# OttoPi05b.net
KiCad netlist of a schematic drawn in EAGLE
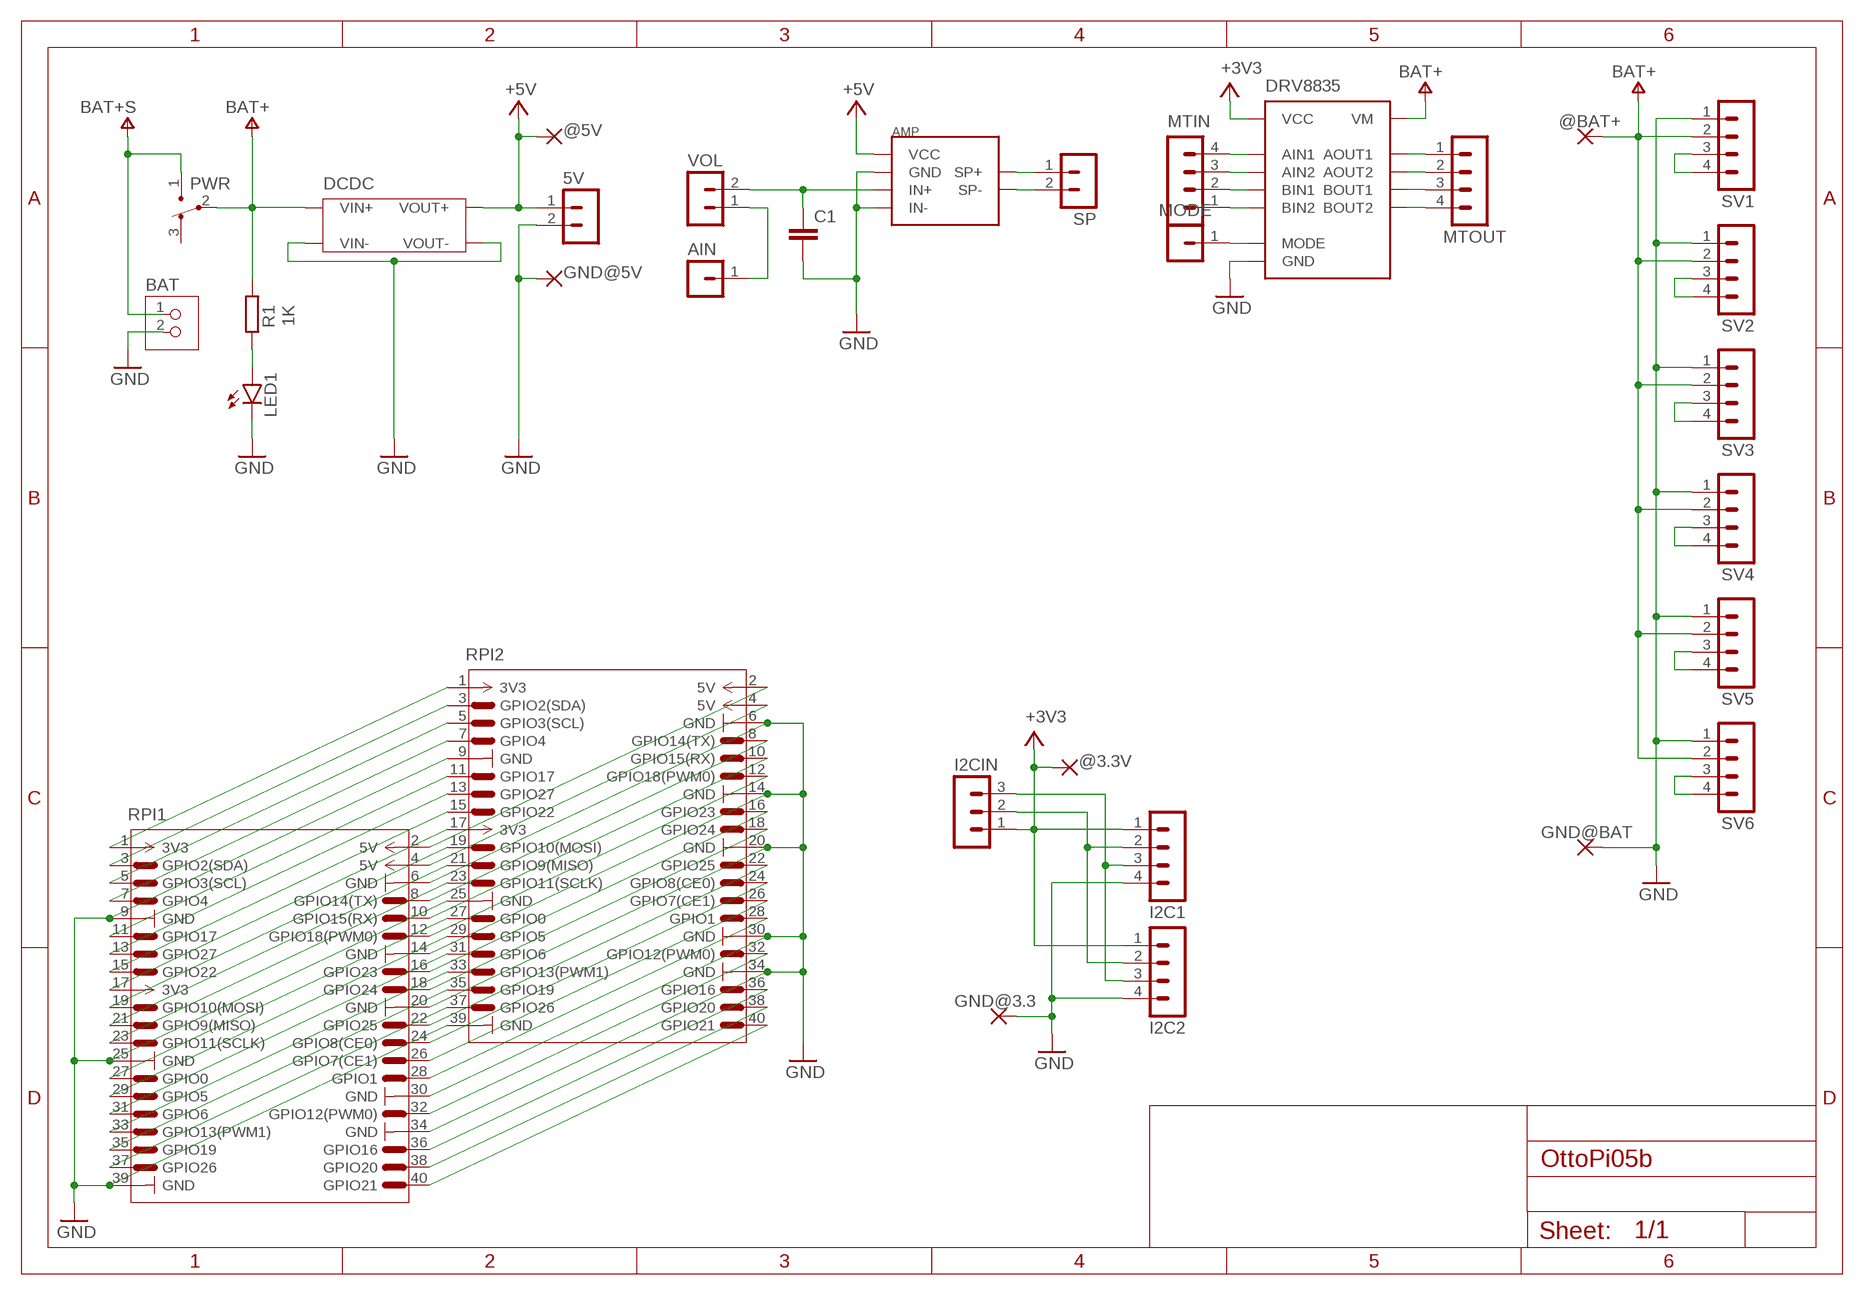
[diagram p0: schematic, sheet 1]

(export (version "E")
  (design (tool "Eeschema 10.0.6"))
  (components
    (comp (ref "5V")
      (value "MA02-1")
      (footprint "eagle-import:MA02-1")
      (libsource (lib "eagle-import") (part "MA02-1"))
    )
    (comp (ref "@3.3V")
      (value "2,15/1,0")
      (footprint "eagle-import:2,15_1,0")
      (libsource (lib "eagle-import") (part "2,15/1,0"))
    )
    (comp (ref "@5V")
      (value "2,15/1,0")
      (footprint "eagle-import:2,15_1,0")
      (libsource (lib "eagle-import") (part "2,15/1,0"))
    )
    (comp (ref "@BAT+")
      (value "2,15/1,0")
      (footprint "eagle-import:2,15_1,0")
      (libsource (lib "eagle-import") (part "2,15/1,0"))
    )
    (comp (ref "AIN")
      (value "MA01-1")
      (footprint "eagle-import:MA01-1")
      (libsource (lib "eagle-import") (part "MA01-1"))
    )
    (comp (ref "AMP")
      (value "PAM8012MOD")
      (footprint "eagle-import:PAM8012MOD-A")
      (libsource (lib "eagle-import") (part "PAM8012MOD"))
    )
    (comp (ref "BAT")
      (value "JST-PH2")
      (footprint "eagle-import:JST-PH2")
      (libsource (lib "eagle-import") (part "JST-PH2"))
    )
    (comp (ref "C1")
      (value "C-EU025-024X044")
      (footprint "eagle-import:C025-024X044")
      (libsource (lib "eagle-import") (part "C-EU025-024X044"))
    )
    (comp (ref "DCDC")
      (value "DCDC-5V_28V-2A")
      (footprint "eagle-import:DCDC-5V_28V-2A")
      (libsource (lib "eagle-import") (part "DCDC-5V_28V-2A"))
    )
    (comp (ref "DRV8835")
      (value "DRV8835MOD")
      (footprint "eagle-import:DRV8835MOD")
      (libsource (lib "eagle-import") (part "DRV8835MOD"))
    )
    (comp (ref "GND@3.3")
      (value "2,15/1,0")
      (footprint "eagle-import:2,15_1,0")
      (libsource (lib "eagle-import") (part "2,15/1,0"))
    )
    (comp (ref "GND@5V")
      (value "2,15/1,0")
      (footprint "eagle-import:2,15_1,0")
      (libsource (lib "eagle-import") (part "2,15/1,0"))
    )
    (comp (ref "GND@BAT")
      (value "2,15/1,0")
      (footprint "eagle-import:2,15_1,0")
      (libsource (lib "eagle-import") (part "2,15/1,0"))
    )
    (comp (ref "I2C1")
      (value "MA04-1")
      (footprint "eagle-import:MA04-1")
      (libsource (lib "eagle-import") (part "MA04-1"))
    )
    (comp (ref "I2C2")
      (value "MA04-1")
      (footprint "eagle-import:MA04-1")
      (libsource (lib "eagle-import") (part "MA04-1"))
    )
    (comp (ref "I2CIN")
      (value "MA03-1")
      (footprint "eagle-import:MA03-1")
      (libsource (lib "eagle-import") (part "MA03-1"))
    )
    (comp (ref "LED1")
      (value "LED3MM")
      (footprint "eagle-import:LED3MM")
      (libsource (lib "eagle-import") (part "LED3MM"))
    )
    (comp (ref "MODE")
      (value "MA01-1")
      (footprint "eagle-import:MA01-1")
      (libsource (lib "eagle-import") (part "MA01-1"))
    )
    (comp (ref "MTIN")
      (value "MA04-1")
      (footprint "eagle-import:MA04-1")
      (libsource (lib "eagle-import") (part "MA04-1"))
    )
    (comp (ref "MTOUT")
      (value "MA04-1")
      (footprint "eagle-import:MA04-1")
      (libsource (lib "eagle-import") (part "MA04-1"))
    )
    (comp (ref "PWR")
      (value "SW3-1")
      (footprint "eagle-import:SW3-1")
      (fields (field (name "MF") "HiLetgo"))
      (libsource (lib "eagle-import") (part "SW3-1"))
    )
    (comp (ref "R1")
      (value "1K")
      (footprint "eagle-import:0204_7")
      (libsource (lib "eagle-import") (part "R-EU_0204/7"))
    )
    (comp (ref "RPI1")
      (value "RPI-PIN")
      (footprint "eagle-import:RPI-PIN")
      (libsource (lib "eagle-import") (part "RPI-PIN"))
    )
    (comp (ref "RPI2")
      (value "RPI-PIN")
      (footprint "eagle-import:RPI-PIN")
      (libsource (lib "eagle-import") (part "RPI-PIN"))
    )
    (comp (ref "SP")
      (value "MA02-1")
      (footprint "eagle-import:MA02-1")
      (libsource (lib "eagle-import") (part "MA02-1"))
    )
    (comp (ref "SV1")
      (value "MA04-1")
      (footprint "eagle-import:MA04-1")
      (libsource (lib "eagle-import") (part "MA04-1"))
    )
    (comp (ref "SV2")
      (value "MA04-1")
      (footprint "eagle-import:MA04-1")
      (libsource (lib "eagle-import") (part "MA04-1"))
    )
    (comp (ref "SV3")
      (value "MA04-1")
      (footprint "eagle-import:MA04-1")
      (libsource (lib "eagle-import") (part "MA04-1"))
    )
    (comp (ref "SV4")
      (value "MA04-1")
      (footprint "eagle-import:MA04-1")
      (libsource (lib "eagle-import") (part "MA04-1"))
    )
    (comp (ref "SV5")
      (value "MA04-1")
      (footprint "eagle-import:MA04-1")
      (libsource (lib "eagle-import") (part "MA04-1"))
    )
    (comp (ref "SV6")
      (value "MA04-1")
      (footprint "eagle-import:MA04-1")
      (libsource (lib "eagle-import") (part "MA04-1"))
    )
    (comp (ref "VOL")
      (value "MA02-1")
      (footprint "eagle-import:MA02-1")
      (libsource (lib "eagle-import") (part "MA02-1"))
    )
  )
  (nets
    (net (code "1") (name "+3V3") (class "Default")
      (node (ref "@3.3V") (pin "1") (pinfunction "P_1") (pintype "passive"))
      (node (ref "DRV8835") (pin "VCC") (pinfunction "VCC_VCC") (pintype "input"))
      (node (ref "I2C1") (pin "1") (pinfunction "1_1") (pintype "passive"))
      (node (ref "I2C2") (pin "1") (pinfunction "1_1") (pintype "passive"))
      (node (ref "I2CIN") (pin "1") (pinfunction "1_1") (pintype "passive"))
    )
    (net (code "2") (name "+5V") (class "Default")
      (node (ref "5V") (pin "1") (pinfunction "1_1") (pintype "passive"))
      (node (ref "@5V") (pin "1") (pinfunction "P_1") (pintype "passive"))
      (node (ref "AMP") (pin "V+") (pinfunction "VCC_V+") (pintype "power_in"))
      (node (ref "DCDC") (pin "VOUT+") (pinfunction "VOUT+_VOUT+") (pintype "power_in"))
    )
    (net (code "3") (name "BAT+") (class "Default")
      (node (ref "@BAT+") (pin "1") (pinfunction "P_1") (pintype "passive"))
      (node (ref "DCDC") (pin "VIN+") (pinfunction "VIN+_VIN+") (pintype "power_in"))
      (node (ref "DRV8835") (pin "VM") (pinfunction "VM_VM") (pintype "input"))
      (node (ref "PWR") (pin "2") (pinfunction "2_2") (pintype "passive"))
      (node (ref "R1") (pin "2") (pinfunction "2_2") (pintype "passive"))
      (node (ref "SV1") (pin "2") (pinfunction "2_2") (pintype "passive"))
      (node (ref "SV2") (pin "2") (pinfunction "2_2") (pintype "passive"))
      (node (ref "SV3") (pin "2") (pinfunction "2_2") (pintype "passive"))
      (node (ref "SV4") (pin "2") (pinfunction "2_2") (pintype "passive"))
      (node (ref "SV5") (pin "2") (pinfunction "2_2") (pintype "passive"))
      (node (ref "SV6") (pin "2") (pinfunction "2_2") (pintype "passive"))
    )
    (net (code "4") (name "BAT+S") (class "Default")
      (node (ref "BAT") (pin "1") (pinfunction "1_1") (pintype "passive"))
      (node (ref "PWR") (pin "1") (pinfunction "1_1") (pintype "passive"))
    )
    (net (code "5") (name "GND") (class "Default")
      (node (ref "5V") (pin "2") (pinfunction "2_2") (pintype "passive"))
      (node (ref "AMP") (pin "GND") (pinfunction "GND_GND") (pintype "power_in"))
      (node (ref "AMP") (pin "IN-") (pinfunction "IN-_IN-") (pintype "input"))
      (node (ref "BAT") (pin "2") (pinfunction "2_2") (pintype "passive"))
      (node (ref "C1") (pin "2") (pinfunction "2_2") (pintype "passive"))
      (node (ref "DCDC") (pin "VIN-") (pinfunction "VIN-_VIN-") (pintype "power_in"))
      (node (ref "DCDC") (pin "VOUT-") (pinfunction "VOUT-_VOUT-") (pintype "power_in"))
      (node (ref "DRV8835") (pin "GND") (pinfunction "GND_GND") (pintype "power_in"))
      (node (ref "GND@3.3") (pin "1") (pinfunction "P_1") (pintype "passive"))
      (node (ref "GND@5V") (pin "1") (pinfunction "P_1") (pintype "passive"))
      (node (ref "GND@BAT") (pin "1") (pinfunction "P_1") (pintype "passive"))
      (node (ref "I2C1") (pin "4") (pinfunction "4_4") (pintype "passive"))
      (node (ref "I2C2") (pin "4") (pinfunction "4_4") (pintype "passive"))
      (node (ref "LED1") (pin "K") (pinfunction "C_K") (pintype "passive"))
      (node (ref "RPI1") (pin "14") (pinfunction "GND_14") (pintype "passive"))
      (node (ref "RPI1") (pin "20") (pinfunction "GND_20") (pintype "passive"))
      (node (ref "RPI1") (pin "25") (pinfunction "GND_25") (pintype "passive"))
      (node (ref "RPI1") (pin "30") (pinfunction "GND_30") (pintype "passive"))
      (node (ref "RPI1") (pin "34") (pinfunction "GND_34") (pintype "passive"))
      (node (ref "RPI1") (pin "39") (pinfunction "GND_39") (pintype "passive"))
      (node (ref "RPI1") (pin "6") (pinfunction "GND_6") (pintype "passive"))
      (node (ref "RPI1") (pin "9") (pinfunction "GND_9") (pintype "passive"))
      (node (ref "RPI2") (pin "14") (pinfunction "GND_14") (pintype "passive"))
      (node (ref "RPI2") (pin "20") (pinfunction "GND_20") (pintype "passive"))
      (node (ref "RPI2") (pin "25") (pinfunction "GND_25") (pintype "passive"))
      (node (ref "RPI2") (pin "30") (pinfunction "GND_30") (pintype "passive"))
      (node (ref "RPI2") (pin "34") (pinfunction "GND_34") (pintype "passive"))
      (node (ref "RPI2") (pin "39") (pinfunction "GND_39") (pintype "passive"))
      (node (ref "RPI2") (pin "6") (pinfunction "GND_6") (pintype "passive"))
      (node (ref "RPI2") (pin "9") (pinfunction "GND_9") (pintype "passive"))
      (node (ref "SV1") (pin "1") (pinfunction "1_1") (pintype "passive"))
      (node (ref "SV2") (pin "1") (pinfunction "1_1") (pintype "passive"))
      (node (ref "SV3") (pin "1") (pinfunction "1_1") (pintype "passive"))
      (node (ref "SV4") (pin "1") (pinfunction "1_1") (pintype "passive"))
      (node (ref "SV5") (pin "1") (pinfunction "1_1") (pintype "passive"))
      (node (ref "SV6") (pin "1") (pinfunction "1_1") (pintype "passive"))
    )
    (net (code "6") (name "Net-(AIN-Pad1)") (class "Default")
      (node (ref "AIN") (pin "1") (pinfunction "1_1") (pintype "passive"))
      (node (ref "VOL") (pin "1") (pinfunction "1_1") (pintype "passive"))
    )
    (net (code "7") (name "Net-(AMP-PadIN+)") (class "Default")
      (node (ref "AMP") (pin "IN+") (pinfunction "IN+_IN+") (pintype "input"))
      (node (ref "C1") (pin "1") (pinfunction "1_1") (pintype "passive"))
      (node (ref "VOL") (pin "2") (pinfunction "2_2") (pintype "passive"))
    )
    (net (code "8") (name "Net-(AMP-SP+)") (class "Default")
      (node (ref "AMP") (pin "SP+@1") (pinfunction "SP+_SP+@1") (pintype "output"))
      (node (ref "SP") (pin "1") (pinfunction "1_1") (pintype "passive"))
    )
    (net (code "9") (name "Net-(AMP-SP-)") (class "Default")
      (node (ref "AMP") (pin "SP-@1") (pinfunction "SP-_SP-@1") (pintype "output"))
      (node (ref "SP") (pin "2") (pinfunction "2_2") (pintype "passive"))
    )
    (net (code "10") (name "Net-(DRV8835-PadAIN1)") (class "Default")
      (node (ref "DRV8835") (pin "AIN1") (pinfunction "AIN1_AIN1") (pintype "input"))
      (node (ref "MTIN") (pin "4") (pinfunction "4_4") (pintype "passive"))
    )
    (net (code "11") (name "Net-(DRV8835-PadAIN2)") (class "Default")
      (node (ref "DRV8835") (pin "AIN2") (pinfunction "AIN2_AIN2") (pintype "input"))
      (node (ref "MTIN") (pin "3") (pinfunction "3_3") (pintype "passive"))
    )
    (net (code "12") (name "Net-(DRV8835-PadAOUT1)") (class "Default")
      (node (ref "DRV8835") (pin "AOUT1") (pinfunction "AOUT1_AOUT1") (pintype "output"))
      (node (ref "MTOUT") (pin "1") (pinfunction "1_1") (pintype "passive"))
    )
    (net (code "13") (name "Net-(DRV8835-PadAOUT2)") (class "Default")
      (node (ref "DRV8835") (pin "AOUT2") (pinfunction "AOUT2_AOUT2") (pintype "output"))
      (node (ref "MTOUT") (pin "2") (pinfunction "2_2") (pintype "passive"))
    )
    (net (code "14") (name "Net-(DRV8835-PadBIN1)") (class "Default")
      (node (ref "DRV8835") (pin "BIN1") (pinfunction "BIN1_BIN1") (pintype "input"))
      (node (ref "MTIN") (pin "2") (pinfunction "2_2") (pintype "passive"))
    )
    (net (code "15") (name "Net-(DRV8835-PadBIN2)") (class "Default")
      (node (ref "DRV8835") (pin "BIN2") (pinfunction "BIN2_BIN2") (pintype "input"))
      (node (ref "MTIN") (pin "1") (pinfunction "1_1") (pintype "passive"))
    )
    (net (code "16") (name "Net-(DRV8835-PadBOUT1)") (class "Default")
      (node (ref "DRV8835") (pin "BOUT1") (pinfunction "BOUT1_BOUT1") (pintype "output"))
      (node (ref "MTOUT") (pin "3") (pinfunction "3_3") (pintype "passive"))
    )
    (net (code "17") (name "Net-(DRV8835-PadBOUT2)") (class "Default")
      (node (ref "DRV8835") (pin "BOUT2") (pinfunction "BOUT2_BOUT2") (pintype "output"))
      (node (ref "MTOUT") (pin "4") (pinfunction "4_4") (pintype "passive"))
    )
    (net (code "18") (name "Net-(DRV8835-PadMODE)") (class "Default")
      (node (ref "DRV8835") (pin "MODE") (pinfunction "MODE_MODE") (pintype "input"))
      (node (ref "MODE") (pin "1") (pinfunction "1_1") (pintype "passive"))
    )
    (net (code "19") (name "Net-(I2C1-Pad2)") (class "Default")
      (node (ref "I2C1") (pin "2") (pinfunction "2_2") (pintype "passive"))
      (node (ref "I2C2") (pin "2") (pinfunction "2_2") (pintype "passive"))
      (node (ref "I2CIN") (pin "2") (pinfunction "2_2") (pintype "passive"))
    )
    (net (code "20") (name "Net-(I2C1-Pad3)") (class "Default")
      (node (ref "I2C1") (pin "3") (pinfunction "3_3") (pintype "passive"))
      (node (ref "I2C2") (pin "3") (pinfunction "3_3") (pintype "passive"))
      (node (ref "I2CIN") (pin "3") (pinfunction "3_3") (pintype "passive"))
    )
    (net (code "21") (name "Net-(LED1-PadA)") (class "Default")
      (node (ref "LED1") (pin "A") (pinfunction "A_A") (pintype "passive"))
      (node (ref "R1") (pin "1") (pinfunction "1_1") (pintype "passive"))
    )
    (net (code "22") (name "Net-(RPI1-3V3-Pad1)") (class "Default")
      (node (ref "RPI1") (pin "1") (pinfunction "3V3_1") (pintype "passive"))
      (node (ref "RPI2") (pin "1") (pinfunction "3V3_1") (pintype "passive"))
    )
    (net (code "23") (name "Net-(RPI1-3V3-Pad17)") (class "Default")
      (node (ref "RPI1") (pin "17") (pinfunction "3V3_17") (pintype "passive"))
      (node (ref "RPI2") (pin "17") (pinfunction "3V3_17") (pintype "passive"))
    )
    (net (code "24") (name "Net-(RPI1-5V-Pad2)") (class "Default")
      (node (ref "RPI1") (pin "2") (pinfunction "5V_2") (pintype "passive"))
      (node (ref "RPI2") (pin "2") (pinfunction "5V_2") (pintype "passive"))
    )
    (net (code "25") (name "Net-(RPI1-5V-Pad4)") (class "Default")
      (node (ref "RPI1") (pin "4") (pinfunction "5V_4") (pintype "passive"))
      (node (ref "RPI2") (pin "4") (pinfunction "5V_4") (pintype "passive"))
    )
    (net (code "26") (name "Net-(RPI1-GPIO0)") (class "Default")
      (node (ref "RPI1") (pin "27") (pinfunction "GPIO0_27") (pintype "passive"))
      (node (ref "RPI2") (pin "27") (pinfunction "GPIO0_27") (pintype "passive"))
    )
    (net (code "27") (name "Net-(RPI1-GPIO1)") (class "Default")
      (node (ref "RPI1") (pin "28") (pinfunction "GPIO1_28") (pintype "passive"))
      (node (ref "RPI2") (pin "28") (pinfunction "GPIO1_28") (pintype "passive"))
    )
    (net (code "28") (name "Net-(RPI1-GPIO2(SDA))") (class "Default")
      (node (ref "RPI1") (pin "3") (pinfunction "GPIO2(SDA)_3") (pintype "passive"))
      (node (ref "RPI2") (pin "3") (pinfunction "GPIO2(SDA)_3") (pintype "passive"))
    )
    (net (code "29") (name "Net-(RPI1-GPIO3(SCL))") (class "Default")
      (node (ref "RPI1") (pin "5") (pinfunction "GPIO3(SCL)_5") (pintype "passive"))
      (node (ref "RPI2") (pin "5") (pinfunction "GPIO3(SCL)_5") (pintype "passive"))
    )
    (net (code "30") (name "Net-(RPI1-GPIO4)") (class "Default")
      (node (ref "RPI1") (pin "7") (pinfunction "GPIO4_7") (pintype "passive"))
      (node (ref "RPI2") (pin "7") (pinfunction "GPIO4_7") (pintype "passive"))
    )
    (net (code "31") (name "Net-(RPI1-GPIO5)") (class "Default")
      (node (ref "RPI1") (pin "29") (pinfunction "GPIO5_29") (pintype "passive"))
      (node (ref "RPI2") (pin "29") (pinfunction "GPIO5_29") (pintype "passive"))
    )
    (net (code "32") (name "Net-(RPI1-GPIO6)") (class "Default")
      (node (ref "RPI1") (pin "31") (pinfunction "GPIO6_31") (pintype "passive"))
      (node (ref "RPI2") (pin "31") (pinfunction "GPIO6_31") (pintype "passive"))
    )
    (net (code "33") (name "Net-(RPI1-GPIO7(CE1))") (class "Default")
      (node (ref "RPI1") (pin "26") (pinfunction "GPIO7(CE1)_26") (pintype "passive"))
      (node (ref "RPI2") (pin "26") (pinfunction "GPIO7(CE1)_26") (pintype "passive"))
    )
    (net (code "34") (name "Net-(RPI1-GPIO8(CE0))") (class "Default")
      (node (ref "RPI1") (pin "24") (pinfunction "GPIO8(CE0)_24") (pintype "passive"))
      (node (ref "RPI2") (pin "24") (pinfunction "GPIO8(CE0)_24") (pintype "passive"))
    )
    (net (code "35") (name "Net-(RPI1-GPIO9(MISO))") (class "Default")
      (node (ref "RPI1") (pin "21") (pinfunction "GPIO9(MISO)_21") (pintype "passive"))
      (node (ref "RPI2") (pin "21") (pinfunction "GPIO9(MISO)_21") (pintype "passive"))
    )
    (net (code "36") (name "Net-(RPI1-GPIO10(MOSI))") (class "Default")
      (node (ref "RPI1") (pin "19") (pinfunction "GPIO10(MOSI)_19") (pintype "passive"))
      (node (ref "RPI2") (pin "19") (pinfunction "GPIO10(MOSI)_19") (pintype "passive"))
    )
    (net (code "37") (name "Net-(RPI1-GPIO11(SCLK))") (class "Default")
      (node (ref "RPI1") (pin "23") (pinfunction "GPIO11(SCLK)_23") (pintype "passive"))
      (node (ref "RPI2") (pin "23") (pinfunction "GPIO11(SCLK)_23") (pintype "passive"))
    )
    (net (code "38") (name "Net-(RPI1-GPIO12(PWM0))") (class "Default")
      (node (ref "RPI1") (pin "32") (pinfunction "GPIO12(PWM0)_32") (pintype "passive"))
      (node (ref "RPI2") (pin "32") (pinfunction "GPIO12(PWM0)_32") (pintype "passive"))
    )
    (net (code "39") (name "Net-(RPI1-GPIO13(PWM1))") (class "Default")
      (node (ref "RPI1") (pin "33") (pinfunction "GPIO13(PWM1)_33") (pintype "passive"))
      (node (ref "RPI2") (pin "33") (pinfunction "GPIO13(PWM1)_33") (pintype "passive"))
    )
    (net (code "40") (name "Net-(RPI1-GPIO14(TX))") (class "Default")
      (node (ref "RPI1") (pin "8") (pinfunction "GPIO14(TX)_8") (pintype "passive"))
      (node (ref "RPI2") (pin "8") (pinfunction "GPIO14(TX)_8") (pintype "passive"))
    )
    (net (code "41") (name "Net-(RPI1-GPIO15(RX))") (class "Default")
      (node (ref "RPI1") (pin "10") (pinfunction "GPIO15(RX)_10") (pintype "passive"))
      (node (ref "RPI2") (pin "10") (pinfunction "GPIO15(RX)_10") (pintype "passive"))
    )
    (net (code "42") (name "Net-(RPI1-GPIO16)") (class "Default")
      (node (ref "RPI1") (pin "36") (pinfunction "GPIO16_36") (pintype "passive"))
      (node (ref "RPI2") (pin "36") (pinfunction "GPIO16_36") (pintype "passive"))
    )
    (net (code "43") (name "Net-(RPI1-GPIO17)") (class "Default")
      (node (ref "RPI1") (pin "11") (pinfunction "GPIO17_11") (pintype "passive"))
      (node (ref "RPI2") (pin "11") (pinfunction "GPIO17_11") (pintype "passive"))
    )
    (net (code "44") (name "Net-(RPI1-GPIO18(PWM0))") (class "Default")
      (node (ref "RPI1") (pin "12") (pinfunction "GPIO18(PWM0)_12") (pintype "passive"))
      (node (ref "RPI2") (pin "12") (pinfunction "GPIO18(PWM0)_12") (pintype "passive"))
    )
    (net (code "45") (name "Net-(RPI1-GPIO19)") (class "Default")
      (node (ref "RPI1") (pin "35") (pinfunction "GPIO19_35") (pintype "passive"))
      (node (ref "RPI2") (pin "35") (pinfunction "GPIO19_35") (pintype "passive"))
    )
    (net (code "46") (name "Net-(RPI1-GPIO20)") (class "Default")
      (node (ref "RPI1") (pin "38") (pinfunction "GPIO20_38") (pintype "passive"))
      (node (ref "RPI2") (pin "38") (pinfunction "GPIO20_38") (pintype "passive"))
    )
    (net (code "47") (name "Net-(RPI1-GPIO21)") (class "Default")
      (node (ref "RPI1") (pin "40") (pinfunction "GPIO21_40") (pintype "passive"))
      (node (ref "RPI2") (pin "40") (pinfunction "GPIO21_40") (pintype "passive"))
    )
    (net (code "48") (name "Net-(RPI1-GPIO22)") (class "Default")
      (node (ref "RPI1") (pin "15") (pinfunction "GPIO22_15") (pintype "passive"))
      (node (ref "RPI2") (pin "15") (pinfunction "GPIO22_15") (pintype "passive"))
    )
    (net (code "49") (name "Net-(RPI1-GPIO23)") (class "Default")
      (node (ref "RPI1") (pin "16") (pinfunction "GPIO23_16") (pintype "passive"))
      (node (ref "RPI2") (pin "16") (pinfunction "GPIO23_16") (pintype "passive"))
    )
    (net (code "50") (name "Net-(RPI1-GPIO24)") (class "Default")
      (node (ref "RPI1") (pin "18") (pinfunction "GPIO24_18") (pintype "passive"))
      (node (ref "RPI2") (pin "18") (pinfunction "GPIO24_18") (pintype "passive"))
    )
    (net (code "51") (name "Net-(RPI1-GPIO25)") (class "Default")
      (node (ref "RPI1") (pin "22") (pinfunction "GPIO25_22") (pintype "passive"))
      (node (ref "RPI2") (pin "22") (pinfunction "GPIO25_22") (pintype "passive"))
    )
    (net (code "52") (name "Net-(RPI1-GPIO26)") (class "Default")
      (node (ref "RPI1") (pin "37") (pinfunction "GPIO26_37") (pintype "passive"))
      (node (ref "RPI2") (pin "37") (pinfunction "GPIO26_37") (pintype "passive"))
    )
    (net (code "53") (name "Net-(RPI1-GPIO27)") (class "Default")
      (node (ref "RPI1") (pin "13") (pinfunction "GPIO27_13") (pintype "passive"))
      (node (ref "RPI2") (pin "13") (pinfunction "GPIO27_13") (pintype "passive"))
    )
    (net (code "54") (name "Net-(SV1-Pad3)") (class "Default")
      (node (ref "SV1") (pin "3") (pinfunction "3_3") (pintype "passive"))
      (node (ref "SV1") (pin "4") (pinfunction "4_4") (pintype "passive"))
    )
    (net (code "55") (name "Net-(SV2-Pad3)") (class "Default")
      (node (ref "SV2") (pin "3") (pinfunction "3_3") (pintype "passive"))
      (node (ref "SV2") (pin "4") (pinfunction "4_4") (pintype "passive"))
    )
    (net (code "56") (name "Net-(SV3-Pad3)") (class "Default")
      (node (ref "SV3") (pin "3") (pinfunction "3_3") (pintype "passive"))
      (node (ref "SV3") (pin "4") (pinfunction "4_4") (pintype "passive"))
    )
    (net (code "57") (name "Net-(SV4-Pad3)") (class "Default")
      (node (ref "SV4") (pin "3") (pinfunction "3_3") (pintype "passive"))
      (node (ref "SV4") (pin "4") (pinfunction "4_4") (pintype "passive"))
    )
    (net (code "58") (name "Net-(SV5-Pad3)") (class "Default")
      (node (ref "SV5") (pin "3") (pinfunction "3_3") (pintype "passive"))
      (node (ref "SV5") (pin "4") (pinfunction "4_4") (pintype "passive"))
    )
    (net (code "59") (name "Net-(SV6-Pad3)") (class "Default")
      (node (ref "SV6") (pin "3") (pinfunction "3_3") (pintype "passive"))
      (node (ref "SV6") (pin "4") (pinfunction "4_4") (pintype "passive"))
    )
    (net (code "60") (name "unconnected-(PWR-Pad3)") (class "Default")
      (node (ref "PWR") (pin "3") (pinfunction "3_3") (pintype "passive"))
    )
  )
)
